# battery_voltage-meas.net
KiCad netlist of a schematic drawn in Altium Designer
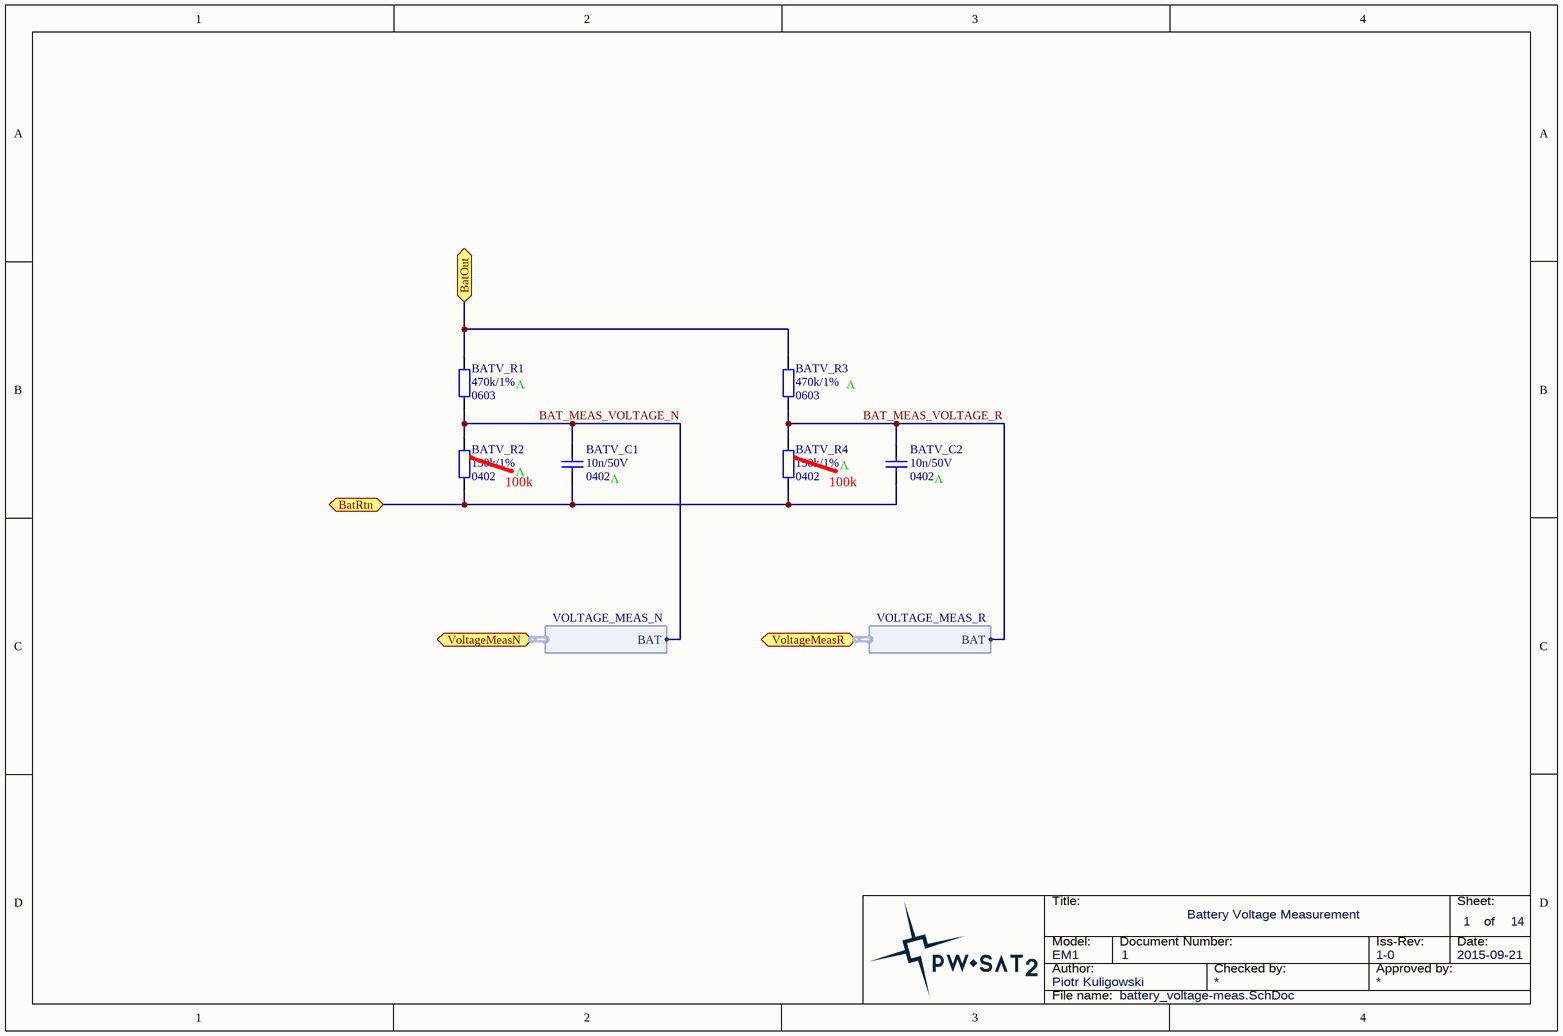
[diagram p0: battery_voltage-meas.SchDoc]

(export (version "E")
  (design (tool "Eeschema 10.0.6"))
  (components
    (comp (ref "BATV_C1")
      (value "10n/50V")
      (footprint "SMD_Capacitor_0402")
      (description "Ceramic Cap Murata Automotive 10n/50V X7R 0402")
      (fields
        (field (name "MANUFACTURER") "Murata")
        (field (name "MANUFACTURERPARTNUMBER") "GCM155R71H103KA55D")
        (field (name "PACKAGE") "0402")
      )
      (libsource (lib "capacitors") (part "Cer_GCM155R71H103KA55D"))
    )
    (comp (ref "BATV_C2")
      (value "10n/50V")
      (footprint "SMD_Capacitor_0402")
      (description "Ceramic Cap Murata Automotive 10n/50V X7R 0402")
      (fields
        (field (name "MANUFACTURER") "Murata")
        (field (name "MANUFACTURERPARTNUMBER") "GCM155R71H103KA55D")
        (field (name "PACKAGE") "0402")
      )
      (libsource (lib "capacitors") (part "Cer_GCM155R71H103KA55D"))
    )
    (comp (ref "BATV_R1")
      (value "470k/1%")
      (footprint "SMD_Resistor_0603")
      (description "470k/1% Vishay CRCW 0603 Resistor. 100mW, 100ppm, 75V.")
      (fields
        (field (name "MANUFACTURER") "Vishay")
        (field (name "MANUFACTURERPARTNUMBER") "CRCW0603470KFKxxxx")
        (field (name "PACKAGE") "0603")
      )
      (libsource (lib "resistors") (part "CRCW0603470KFKxxxx"))
    )
    (comp (ref "BATV_R2")
      (value "150k/1%")
      (footprint "SMD_Resistor_0402")
      (description "150k/1% Vishay CRCW 0402 Resistor. 63mW, 100ppm, 50V.")
      (fields
        (field (name "MANUFACTURER") "Vishay")
        (field (name "MANUFACTURERPARTNUMBER") "CRCW0402150KFKxxxx")
        (field (name "PACKAGE") "0402")
      )
      (libsource (lib "resistors") (part "CRCW0402150KFKxxxx"))
    )
    (comp (ref "BATV_R3")
      (value "470k/1%")
      (footprint "SMD_Resistor_0603")
      (description "470k/1% Vishay CRCW 0603 Resistor. 100mW, 100ppm, 75V.")
      (fields
        (field (name "MANUFACTURER") "Vishay")
        (field (name "MANUFACTURERPARTNUMBER") "CRCW0603470KFKxxxx")
        (field (name "PACKAGE") "0603")
      )
      (libsource (lib "resistors") (part "CRCW0603470KFKxxxx"))
    )
    (comp (ref "BATV_R4")
      (value "150k/1%")
      (footprint "SMD_Resistor_0402")
      (description "150k/1% Vishay CRCW 0402 Resistor. 63mW, 100ppm, 50V.")
      (fields
        (field (name "MANUFACTURER") "Vishay")
        (field (name "MANUFACTURERPARTNUMBER") "CRCW0402150KFKxxxx")
        (field (name "PACKAGE") "0402")
      )
      (libsource (lib "resistors") (part "CRCW0402150KFKxxxx"))
    )
  )
  (nets
    (net (code "3") (name "/BAT_MEAS_VOLTAGE_N") (class "Default")
      (node (ref "BATV_C1") (pin "1") (pinfunction "1_1") (pintype "passive"))
      (node (ref "BATV_R1") (pin "2") (pinfunction "2_2") (pintype "passive"))
      (node (ref "BATV_R2") (pin "1") (pinfunction "1_1") (pintype "passive"))
    )
    (net (code "4") (name "/BAT_MEAS_VOLTAGE_R") (class "Default")
      (node (ref "BATV_C2") (pin "1") (pinfunction "1_1") (pintype "passive"))
      (node (ref "BATV_R3") (pin "2") (pinfunction "2_2") (pintype "passive"))
      (node (ref "BATV_R4") (pin "1") (pinfunction "1_1") (pintype "passive"))
    )
    (net (code "5") (name "/BatOut") (class "Default")
      (node (ref "BATV_R1") (pin "1") (pinfunction "1_1") (pintype "passive"))
      (node (ref "BATV_R3") (pin "1") (pinfunction "1_1") (pintype "passive"))
    )
    (net (code "6") (name "/BatRtn") (class "Default")
      (node (ref "BATV_C1") (pin "2") (pinfunction "2_2") (pintype "passive"))
      (node (ref "BATV_C2") (pin "2") (pinfunction "2_2") (pintype "passive"))
      (node (ref "BATV_R2") (pin "2") (pinfunction "2_2") (pintype "passive"))
      (node (ref "BATV_R4") (pin "2") (pinfunction "2_2") (pintype "passive"))
    )
  )
)
